# BMS-S06-V00-IsolatedCAN.net
KiCad netlist of a schematic drawn in Altium Designer
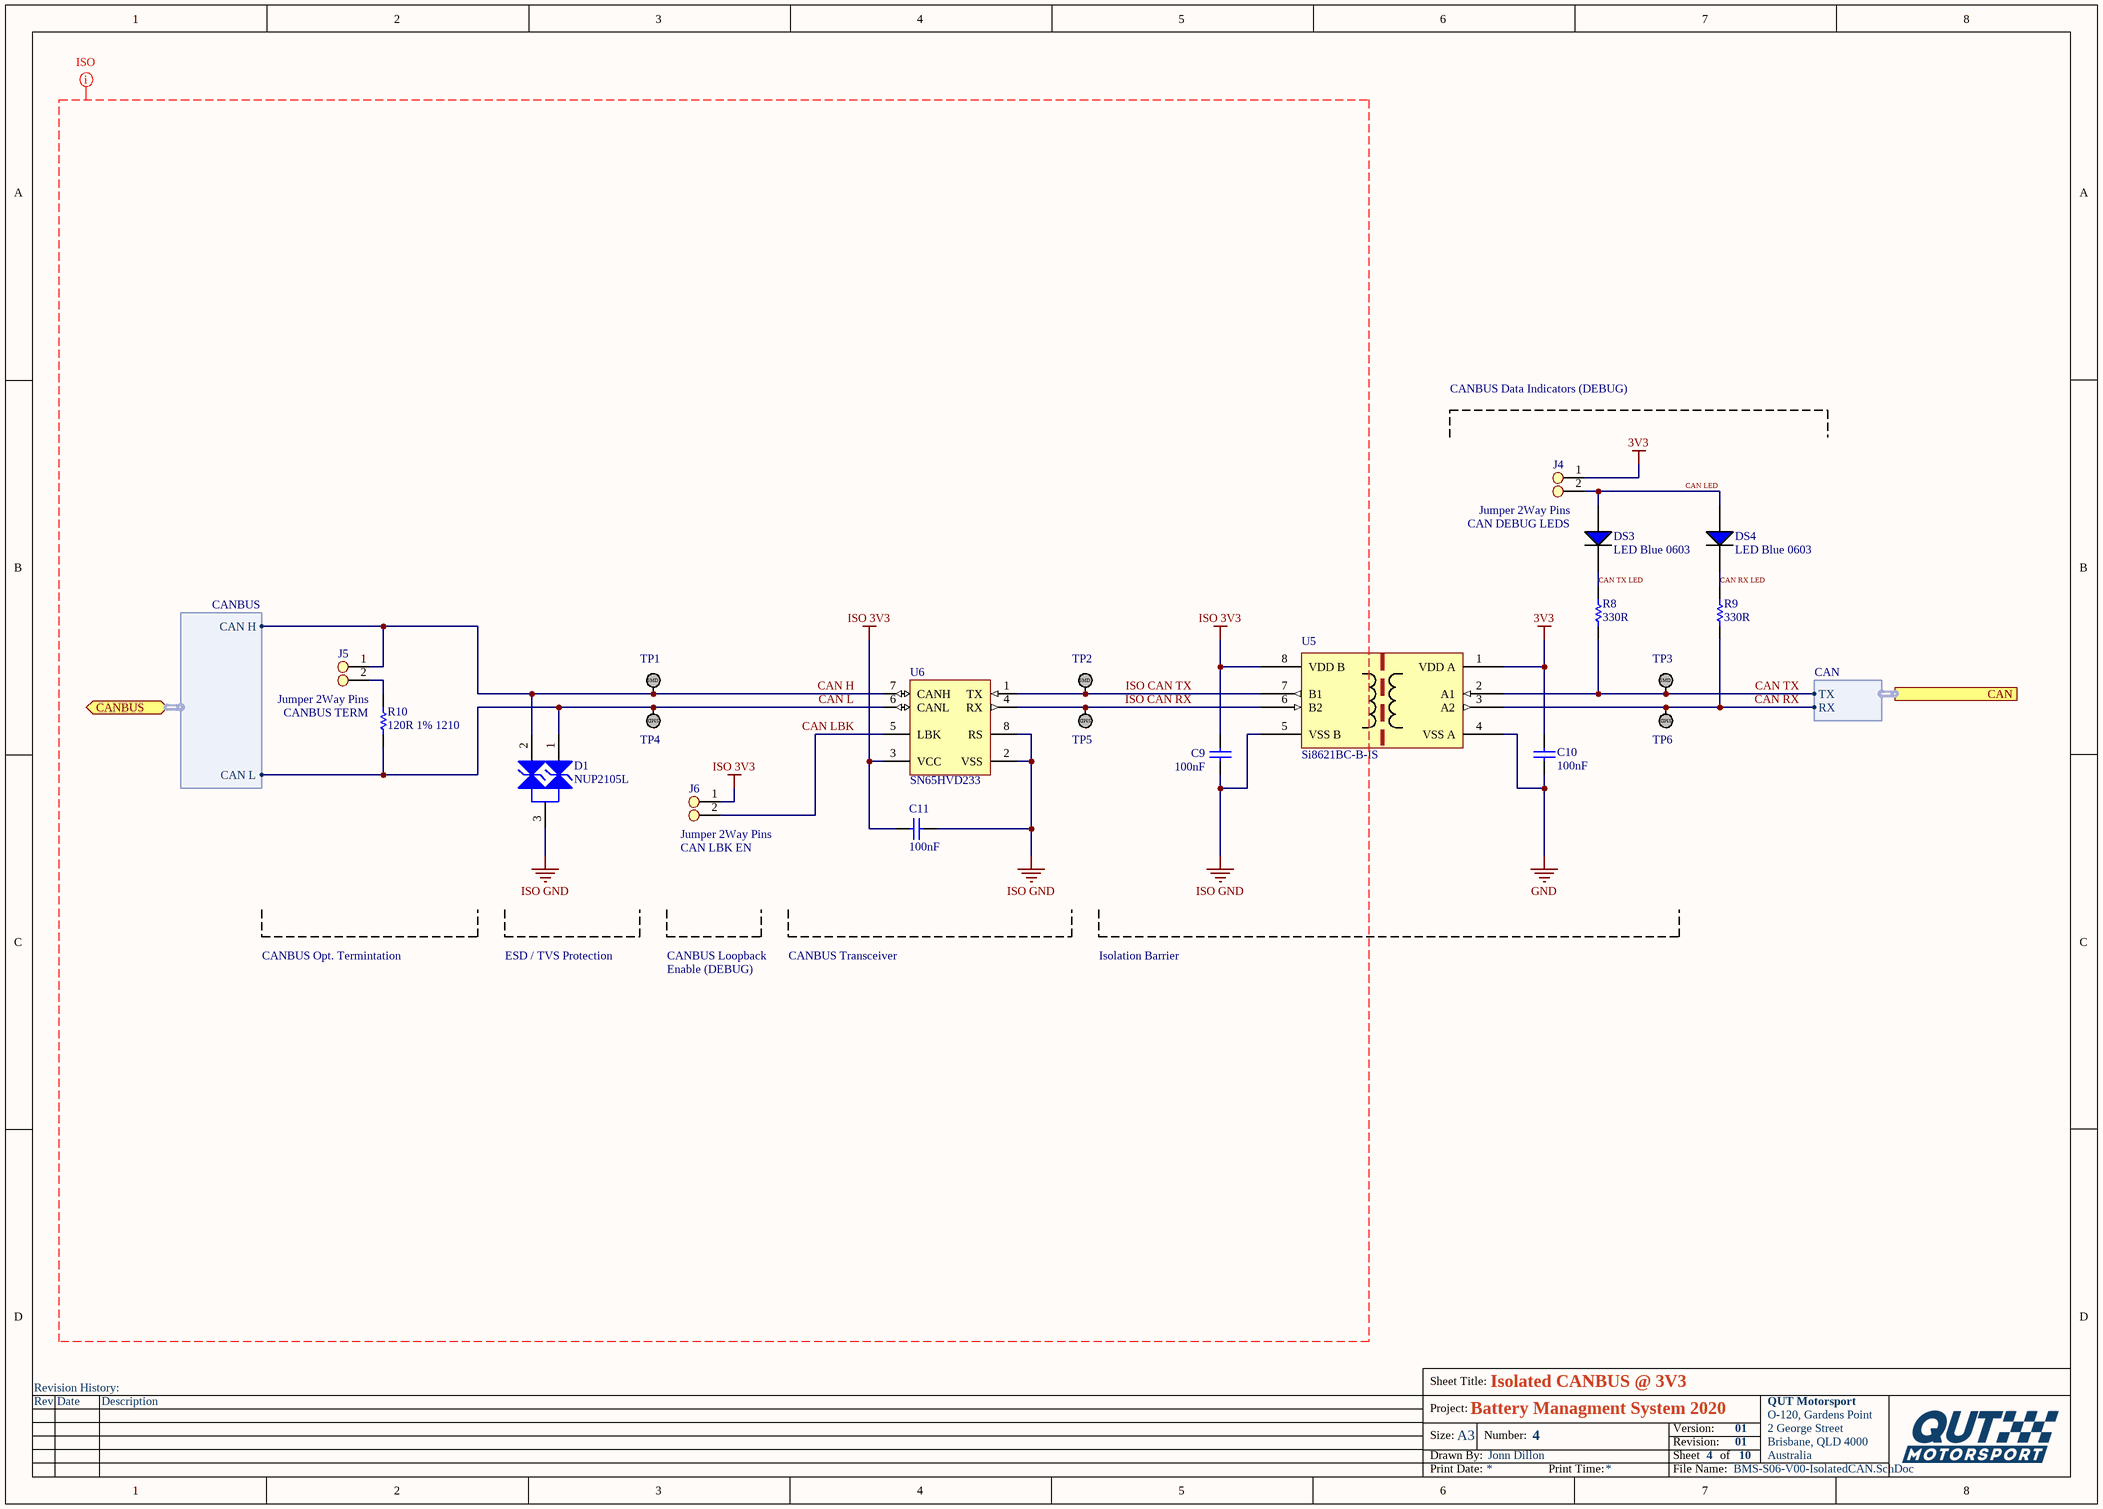
[diagram p0: BMS-S06-V00-IsolatedCAN.SchDoc]

(export (version "E")
  (design (tool "Eeschema 10.0.6"))
  (components
    (comp (ref "C9")
      (value "100nF")
      (footprint "Cap_Ceramic_0603")
      (description "Capacitor, Ceramic, SMD, 100nF, 50V, 5%, X7R, 0603")
      (libsource (lib "StandardCapacitors") (part "100nF 50V 5% X7R 0603"))
    )
    (comp (ref "C10")
      (value "100nF")
      (footprint "Cap_Ceramic_0603")
      (description "Capacitor, Ceramic, SMD, 100nF, 50V, 5%, X7R, 0603")
      (libsource (lib "StandardCapacitors") (part "100nF 50V 5% X7R 0603"))
    )
    (comp (ref "C11")
      (value "100nF")
      (footprint "Cap_Ceramic_0603")
      (description "Capacitor, Ceramic, SMD, 100nF, 50V, 5%, X7R, 0603")
      (libsource (lib "StandardCapacitors") (part "100nF 50V 5% X7R 0603"))
    )
    (comp (ref "D1")
      (value "NUP2105L")
      (footprint "NUP2105L")
      (libsource (lib "QUTMS_CANLibrary") (part "NUP2105L"))
    )
    (comp (ref "DS3")
      (value "LED Blue 0603")
      (footprint "LED BLUE 0603")
      (libsource (lib "QUTMS_LEDLibrary") (part "LED BLUE 0603"))
    )
    (comp (ref "DS4")
      (value "LED Blue 0603")
      (footprint "LED BLUE 0603")
      (libsource (lib "QUTMS_LEDLibrary") (part "LED BLUE 0603"))
    )
    (comp (ref "J4")
      (value "Jumper 2Way Pins")
      (footprint "Jumper_2Way_Pin")
      (description "Jumper 2Way Side Pins")
      (libsource (lib "QUTMS_JumperLibrary") (part "Jumper 2Way Side Pins"))
    )
    (comp (ref "J5")
      (value "Jumper 2Way Pins")
      (footprint "Jumper_2Way_Pin")
      (description "Jumper 2Way Side Pins")
      (libsource (lib "QUTMS_JumperLibrary") (part "Jumper 2Way Side Pins"))
    )
    (comp (ref "J6")
      (value "Jumper 2Way Pins")
      (footprint "Jumper_2Way_Pin")
      (description "Jumper 2Way Side Pins")
      (libsource (lib "QUTMS_JumperLibrary") (part "Jumper 2Way Side Pins"))
    )
    (comp (ref "R8")
      (value "330R")
      (footprint "Res_ThinFilm_0603")
      (description "Resistor, SMD, 330R, 0.1W, 5%, 0603")
      (libsource (lib "StandardResistors") (part "330R 5% 0603"))
    )
    (comp (ref "R9")
      (value "330R")
      (footprint "Res_ThinFilm_0603")
      (description "Resistor, SMD, 330R, 0.1W, 5%, 0603")
      (libsource (lib "StandardResistors") (part "330R 5% 0603"))
    )
    (comp (ref "R10")
      (value "120R 1% 1210")
      (footprint "Res_ThinFilm_1210")
      (description "Resistor, SMD, 120R, 0.25W, 1%, 1210")
      (libsource (lib "StandardResistors") (part "120R 1% 1210"))
    )
    (comp (ref "TP1")
      (value "TestPoint_SMD")
      (footprint "TestPointSMD")
      (libsource (lib "StandardTest") (part "TestPoint_SMD"))
    )
    (comp (ref "TP2")
      (value "TestPoint_SMD")
      (footprint "TestPointSMD")
      (libsource (lib "StandardTest") (part "TestPoint_SMD"))
    )
    (comp (ref "TP3")
      (value "TestPoint_SMD")
      (footprint "TestPointSMD")
      (libsource (lib "StandardTest") (part "TestPoint_SMD"))
    )
    (comp (ref "TP4")
      (value "TestPoint_SMD")
      (footprint "TestPointSMD")
      (libsource (lib "StandardTest") (part "TestPoint_SMD"))
    )
    (comp (ref "TP5")
      (value "TestPoint_SMD")
      (footprint "TestPointSMD")
      (libsource (lib "StandardTest") (part "TestPoint_SMD"))
    )
    (comp (ref "TP6")
      (value "TestPoint_SMD")
      (footprint "TestPointSMD")
      (libsource (lib "StandardTest") (part "TestPoint_SMD"))
    )
    (comp (ref "U5")
      (value "Si8621BC-B-IS")
      (footprint "Si8621BC-B-IS")
      (libsource (lib "QUTMS_IsolatorLibrary") (part "Si8621BC-B-IS"))
    )
    (comp (ref "U6")
      (value "SN65HVD233")
      (footprint "SN65HVD233DR")
      (libsource (lib "QUTMS_CANLibrary") (part "SN65HVD233"))
    )
  )
  (nets
    (net (code "3") (name "/CAN H") (class "Default")
      (node (ref "D1") (pin "2") (pinfunction "2_2") (pintype "passive"))
      (node (ref "J5") (pin "1") (pinfunction "1_1") (pintype "passive"))
      (node (ref "TP1") (pin "1") (pinfunction "1_1") (pintype "passive"))
      (node (ref "U6") (pin "7") (pinfunction "CANH_7") (pintype "bidirectional"))
    )
    (net (code "4") (name "/CAN L") (class "Default")
      (node (ref "D1") (pin "1") (pinfunction "1_1") (pintype "passive"))
      (node (ref "R10") (pin "1") (pinfunction "1_1") (pintype "passive"))
      (node (ref "TP4") (pin "1") (pinfunction "1_1") (pintype "passive"))
      (node (ref "U6") (pin "6") (pinfunction "CANL_6") (pintype "bidirectional"))
    )
    (net (code "5") (name "/CAN LBK") (class "Default")
      (node (ref "J6") (pin "2") (pinfunction "2_2") (pintype "passive"))
      (node (ref "U6") (pin "5") (pinfunction "LBK_5") (pintype "passive"))
    )
    (net (code "6") (name "/CAN LED") (class "Default")
      (node (ref "DS3") (pin "1") (pinfunction "A_1") (pintype "passive"))
      (node (ref "DS4") (pin "1") (pinfunction "A_1") (pintype "passive"))
      (node (ref "J4") (pin "2") (pinfunction "2_2") (pintype "passive"))
    )
    (net (code "7") (name "/CAN RX") (class "Default")
      (node (ref "R9") (pin "1") (pinfunction "1_1") (pintype "passive"))
      (node (ref "TP6") (pin "1") (pinfunction "1_1") (pintype "passive"))
      (node (ref "U5") (pin "3") (pinfunction "A2_3") (pintype "output"))
    )
    (net (code "8") (name "/CAN RX LED") (class "Default")
      (node (ref "DS4") (pin "2") (pinfunction "C_2") (pintype "passive"))
      (node (ref "R9") (pin "2") (pinfunction "2_2") (pintype "passive"))
    )
    (net (code "9") (name "/CAN TX") (class "Default")
      (node (ref "R8") (pin "1") (pinfunction "1_1") (pintype "passive"))
      (node (ref "TP3") (pin "1") (pinfunction "1_1") (pintype "passive"))
      (node (ref "U5") (pin "2") (pinfunction "A1_2") (pintype "input"))
    )
    (net (code "10") (name "/CAN TX LED") (class "Default")
      (node (ref "DS3") (pin "2") (pinfunction "C_2") (pintype "passive"))
      (node (ref "R8") (pin "2") (pinfunction "2_2") (pintype "passive"))
    )
    (net (code "11") (name "/ISO CAN RX") (class "Default")
      (node (ref "TP5") (pin "1") (pinfunction "1_1") (pintype "passive"))
      (node (ref "U5") (pin "6") (pinfunction "B2_6") (pintype "input"))
      (node (ref "U6") (pin "4") (pinfunction "RX_4") (pintype "output"))
    )
    (net (code "12") (name "/ISO CAN TX") (class "Default")
      (node (ref "TP2") (pin "1") (pinfunction "1_1") (pintype "passive"))
      (node (ref "U5") (pin "7") (pinfunction "B1_7") (pintype "output"))
      (node (ref "U6") (pin "1") (pinfunction "TX_1") (pintype "input"))
    )
    (net (code "15") (name "3V3") (class "Default")
      (node (ref "C10") (pin "2") (pinfunction "2_2") (pintype "passive"))
      (node (ref "J4") (pin "1") (pinfunction "1_1") (pintype "passive"))
      (node (ref "U5") (pin "1") (pinfunction "VDD_A_1") (pintype "passive"))
    )
    (net (code "16") (name "GND") (class "Default")
      (node (ref "C10") (pin "1") (pinfunction "1_1") (pintype "passive"))
      (node (ref "U5") (pin "4") (pinfunction "VSS_A_4") (pintype "passive"))
    )
    (net (code "17") (name "ISO 3V3") (class "Default")
      (node (ref "C11") (pin "2") (pinfunction "2_2") (pintype "passive"))
      (node (ref "C9") (pin "2") (pinfunction "2_2") (pintype "passive"))
      (node (ref "J6") (pin "1") (pinfunction "1_1") (pintype "passive"))
      (node (ref "U5") (pin "8") (pinfunction "VDD_B_8") (pintype "passive"))
      (node (ref "U6") (pin "3") (pinfunction "VCC_3") (pintype "passive"))
    )
    (net (code "18") (name "ISO GND") (class "Default")
      (node (ref "C11") (pin "1") (pinfunction "1_1") (pintype "passive"))
      (node (ref "C9") (pin "1") (pinfunction "1_1") (pintype "passive"))
      (node (ref "D1") (pin "3") (pinfunction "3_3") (pintype "passive"))
      (node (ref "U5") (pin "5") (pinfunction "VSS_B_5") (pintype "passive"))
      (node (ref "U6") (pin "2") (pinfunction "VSS_2") (pintype "passive"))
      (node (ref "U6") (pin "8") (pinfunction "RS_8") (pintype "passive"))
    )
    (net (code "19") (name "Net-(J5-Pad2)") (class "Default")
      (node (ref "J5") (pin "2") (pinfunction "2_2") (pintype "passive"))
      (node (ref "R10") (pin "2") (pinfunction "2_2") (pintype "passive"))
    )
  )
)
